# IntegratedSensor.net
KiCad netlist of a schematic drawn in EAGLE
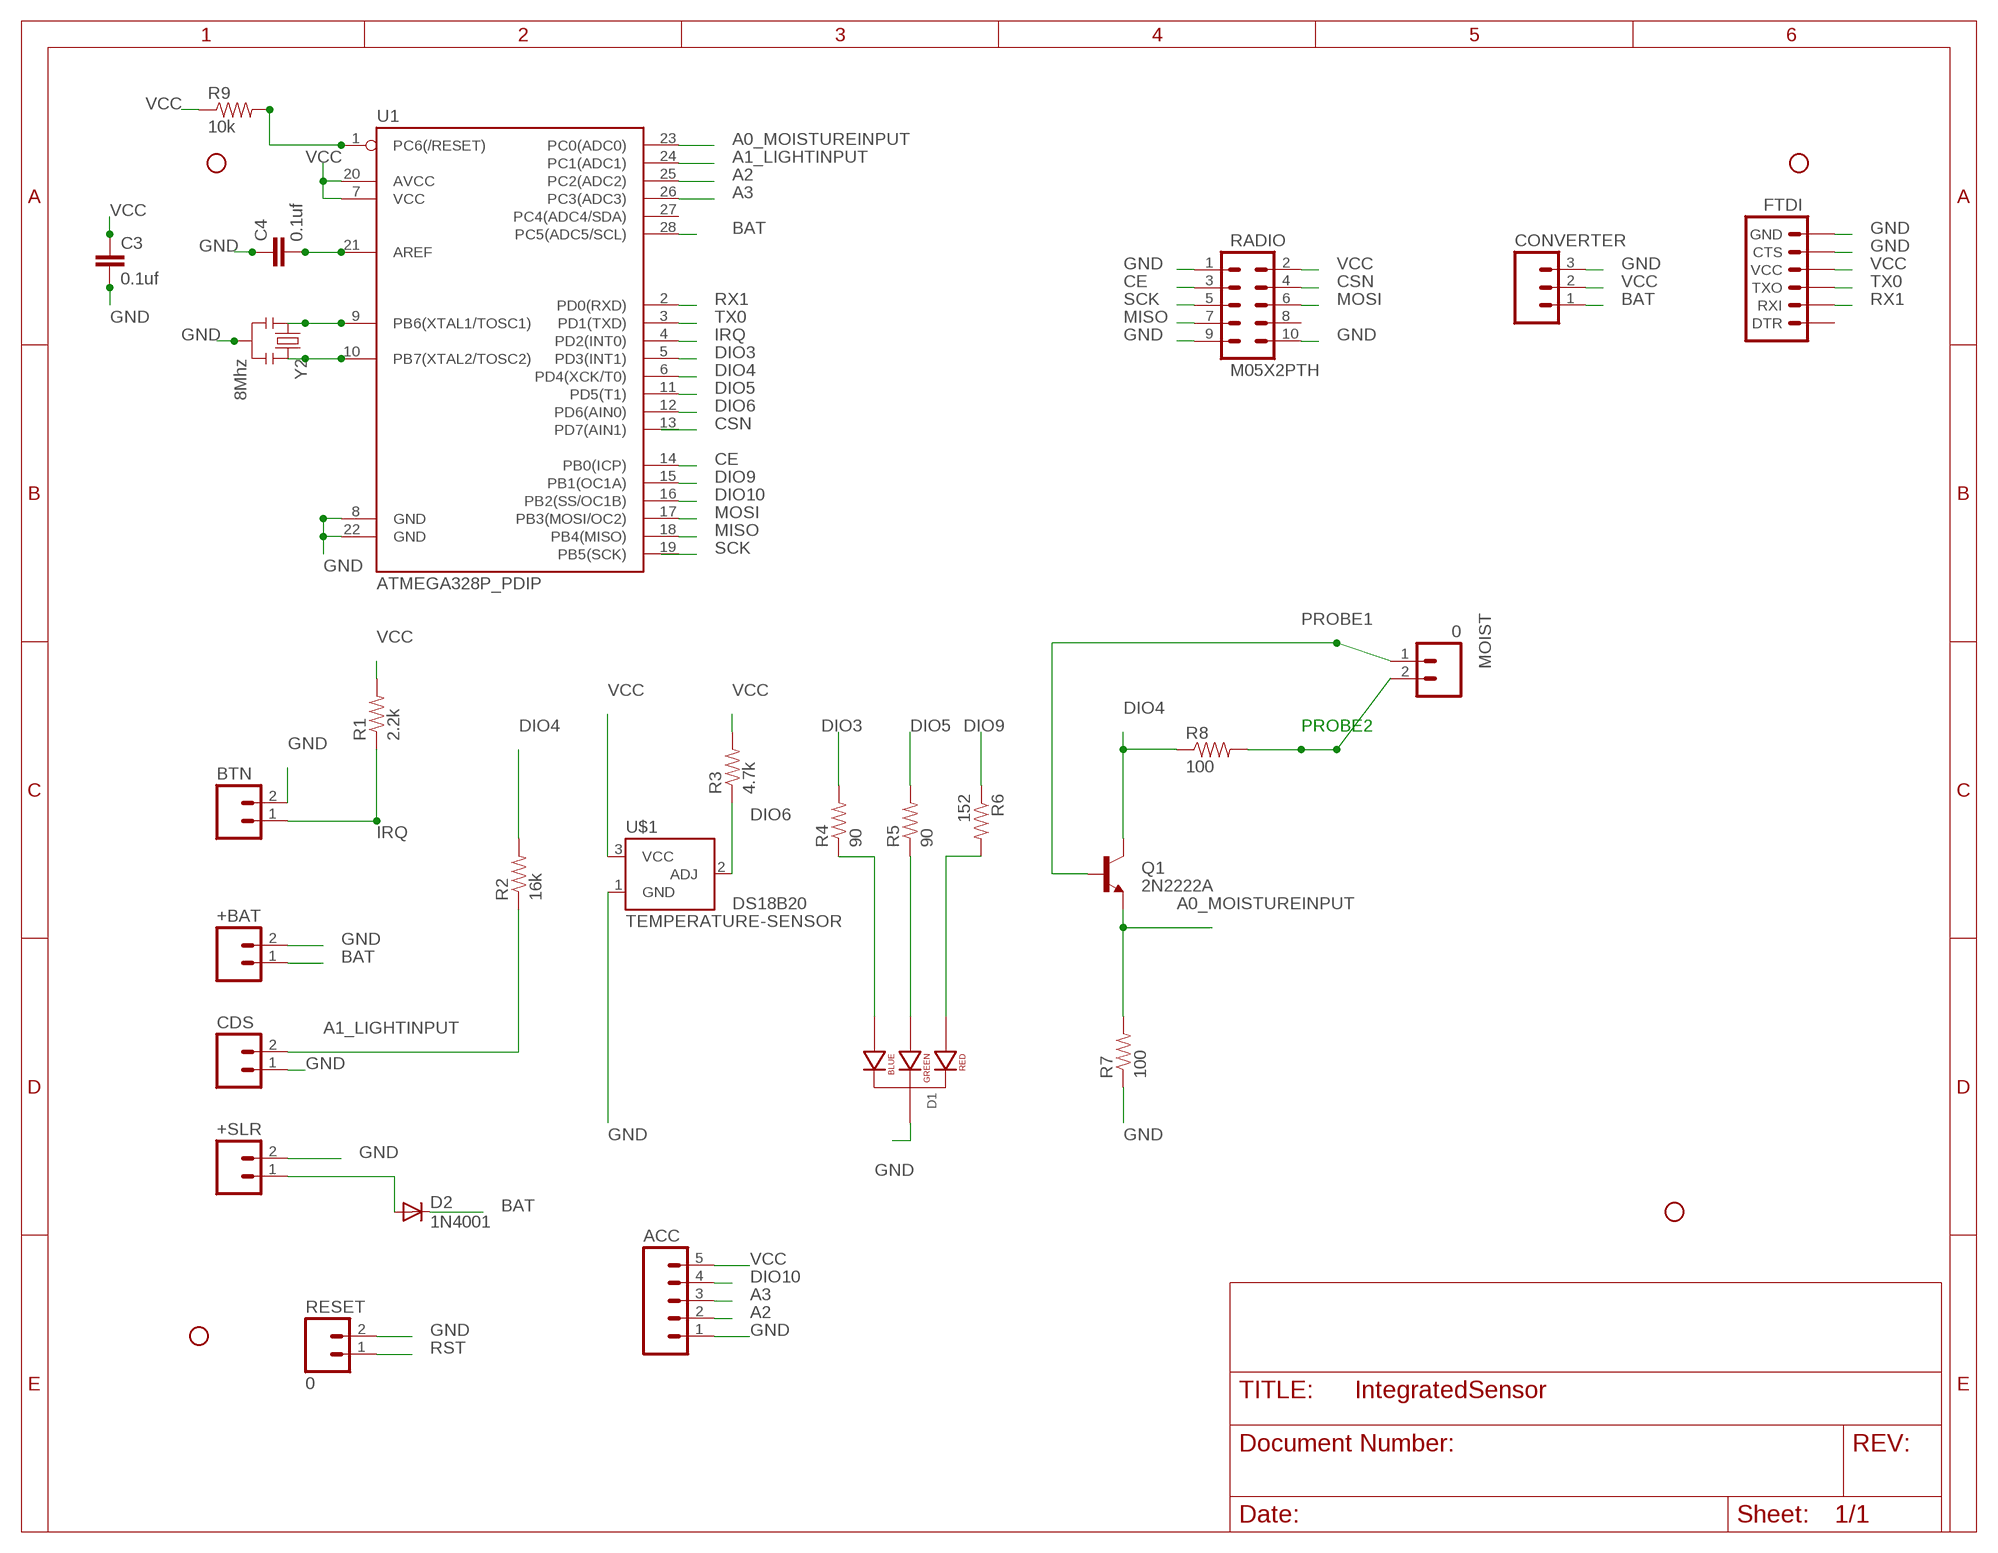
[diagram p0: schematic, sheet 1]

(export (version "E")
  (design (tool "Eeschema 10.0.6"))
  (components
    (comp (ref "+BAT")
      (value "M02PTH")
      (footprint "eagle-import:1X02")
      (libsource (lib "eagle-import") (part "M02PTH"))
    )
    (comp (ref "+SLR")
      (value "M02PTH")
      (footprint "eagle-import:1X02")
      (libsource (lib "eagle-import") (part "M02PTH"))
    )
    (comp (ref "ACC")
      (value "M05PTH")
      (footprint "eagle-import:1X05")
      (libsource (lib "eagle-import") (part "M05PTH"))
    )
    (comp (ref "BTN")
      (value "M02PTH")
      (footprint "eagle-import:1X02")
      (libsource (lib "eagle-import") (part "M02PTH"))
    )
    (comp (ref "C3")
      (value "0.1uf")
      (footprint "eagle-import:CAP-PTH-SMALL")
      (libsource (lib "eagle-import") (part "CAPPTH"))
    )
    (comp (ref "C4")
      (value "0.1uf")
      (footprint "eagle-import:CAP-PTH-SMALL")
      (libsource (lib "eagle-import") (part "CAPPTH"))
    )
    (comp (ref "CDS")
      (value "M02PTH")
      (footprint "eagle-import:1X02")
      (libsource (lib "eagle-import") (part "M02PTH"))
    )
    (comp (ref "CONVERTER")
      (value "M03PTH")
      (footprint "eagle-import:1X03")
      (libsource (lib "eagle-import") (part "M03PTH"))
    )
    (comp (ref "D1")
      (value "LED-RGB-CC-THRUCLEAR")
      (footprint "eagle-import:LED-RGB-THRU")
      (libsource (lib "eagle-import") (part "LED-RGB-CC-THRUCLEAR"))
    )
    (comp (ref "D2")
      (value "1N4001")
      (footprint "eagle-import:DIODE-1N4001")
      (libsource (lib "eagle-import") (part "DIODEPTH"))
    )
    (comp (ref "FTDI")
      (value "ARDUINO_SERIAL_PROGRAMPTH")
      (footprint "eagle-import:1X06")
      (libsource (lib "eagle-import") (part "ARDUINO_SERIAL_PROGRAMPTH"))
    )
    (comp (ref "MOIST")
      (value "0")
      (footprint "eagle-import:1X02")
      (libsource (lib "eagle-import") (part "M02PTH"))
    )
    (comp (ref "Q1")
      (value "2N2222A")
      (footprint "eagle-import:TO-92-AMMO")
      (libsource (lib "eagle-import") (part "TRANSISTOR_NPNTO-92-AMMO"))
    )
    (comp (ref "R1")
      (value "2.2k")
      (footprint "eagle-import:1_6W-RES")
      (libsource (lib "eagle-import") (part "RESISTORPTH-1/6W"))
    )
    (comp (ref "R2")
      (value "16k")
      (footprint "eagle-import:1_6W-RES")
      (libsource (lib "eagle-import") (part "RESISTORPTH-1/6W"))
    )
    (comp (ref "R3")
      (value "4.7k")
      (footprint "eagle-import:1_6W-RES")
      (libsource (lib "eagle-import") (part "RESISTORPTH-1/6W"))
    )
    (comp (ref "R4")
      (value "90")
      (footprint "eagle-import:1_6W-RES")
      (libsource (lib "eagle-import") (part "RESISTORPTH-1/6W"))
    )
    (comp (ref "R5")
      (value "90")
      (footprint "eagle-import:1_6W-RES")
      (libsource (lib "eagle-import") (part "RESISTORPTH-1/6W"))
    )
    (comp (ref "R6")
      (value "152")
      (footprint "eagle-import:1_6W-RES")
      (libsource (lib "eagle-import") (part "RESISTORPTH-1/6W"))
    )
    (comp (ref "R7")
      (value "100")
      (footprint "eagle-import:1_6W-RES")
      (libsource (lib "eagle-import") (part "RESISTORPTH-1/6W"))
    )
    (comp (ref "R8")
      (value "100")
      (footprint "eagle-import:1_6W-RES")
      (libsource (lib "eagle-import") (part "RESISTORPTH-1/6W"))
    )
    (comp (ref "R9")
      (value "10k")
      (footprint "eagle-import:1_6W-RES")
      (libsource (lib "eagle-import") (part "RESISTORPTH-1/6W"))
    )
    (comp (ref "RADIO")
      (value "M05X2PTH")
      (footprint "eagle-import:AVR_ICSP")
      (libsource (lib "eagle-import") (part "M05X2PTH"))
    )
    (comp (ref "RESET")
      (value "0")
      (footprint "eagle-import:1X02")
      (libsource (lib "eagle-import") (part "M02PTH"))
    )
    (comp (ref "STANDOFF1")
      (value "STAND-OFF")
      (footprint "eagle-import:STAND-OFF")
      (libsource (lib "eagle-import") (part "STAND-OFF"))
    )
    (comp (ref "STANDOFF2")
      (value "STAND-OFF")
      (footprint "eagle-import:STAND-OFF")
      (libsource (lib "eagle-import") (part "STAND-OFF"))
    )
    (comp (ref "STANDOFF3")
      (value "STAND-OFF")
      (footprint "eagle-import:STAND-OFF")
      (libsource (lib "eagle-import") (part "STAND-OFF"))
    )
    (comp (ref "STANDOFF4")
      (value "STAND-OFF")
      (footprint "eagle-import:STAND-OFF")
      (libsource (lib "eagle-import") (part "STAND-OFF"))
    )
    (comp (ref "U$1")
      (value "TEMPERATURE-SENSOR")
      (footprint "eagle-import:TO-92")
      (fields (field (name "PARTNAME") "DS18B20"))
      (libsource (lib "eagle-import") (part "TEMPERATURE-SENSOR"))
    )
    (comp (ref "U1")
      (value "ATMEGA328P_PDIP")
      (footprint "eagle-import:DIL28-3")
      (libsource (lib "eagle-import") (part "ATMEGA328P_PDIP"))
    )
    (comp (ref "Y2")
      (value "8Mhz")
      (footprint "eagle-import:RESONATOR-PTH")
      (libsource (lib "eagle-import") (part "RESONATORPTH"))
    )
  )
  (nets
    (net (code "1") (name "/A0_MOISTUREINPUT") (class "Default")
      (node (ref "Q1") (pin "1") (pinfunction "E_1") (pintype "passive"))
      (node (ref "R7") (pin "2") (pinfunction "2_2") (pintype "passive"))
      (node (ref "U1") (pin "23") (pinfunction "PC0(ADC0)_23") (pintype "bidirectional"))
    )
    (net (code "2") (name "/A1_LIGHTINPUT") (class "Default")
      (node (ref "CDS") (pin "2") (pinfunction "2_2") (pintype "passive"))
      (node (ref "R2") (pin "1") (pinfunction "1_1") (pintype "passive"))
      (node (ref "U1") (pin "24") (pinfunction "PC1(ADC1)_24") (pintype "bidirectional"))
    )
    (net (code "3") (name "/A2") (class "Default")
      (node (ref "ACC") (pin "2") (pinfunction "2_2") (pintype "passive"))
      (node (ref "U1") (pin "25") (pinfunction "PC2(ADC2)_25") (pintype "bidirectional"))
    )
    (net (code "4") (name "/A3") (class "Default")
      (node (ref "ACC") (pin "3") (pinfunction "3_3") (pintype "passive"))
      (node (ref "U1") (pin "26") (pinfunction "PC3(ADC3)_26") (pintype "bidirectional"))
    )
    (net (code "5") (name "/BAT") (class "Default")
      (node (ref "+BAT") (pin "1") (pinfunction "1_1") (pintype "passive"))
      (node (ref "CONVERTER") (pin "1") (pinfunction "1_1") (pintype "passive"))
      (node (ref "D2") (pin "C") (pinfunction "C_C") (pintype "passive"))
      (node (ref "U1") (pin "28") (pinfunction "PC5(ADC5/SCL)_28") (pintype "bidirectional"))
    )
    (net (code "6") (name "/CE") (class "Default")
      (node (ref "RADIO") (pin "3") (pinfunction "3_3") (pintype "passive"))
      (node (ref "U1") (pin "14") (pinfunction "PB0(ICP)_14") (pintype "bidirectional"))
    )
    (net (code "7") (name "/CSN") (class "Default")
      (node (ref "RADIO") (pin "4") (pinfunction "4_4") (pintype "passive"))
    )
    (net (code "8") (name "/DIO3") (class "Default")
      (node (ref "R4") (pin "2") (pinfunction "2_2") (pintype "passive"))
      (node (ref "U1") (pin "5") (pinfunction "PD3(INT1)_5") (pintype "bidirectional"))
    )
    (net (code "9") (name "/DIO4") (class "Default")
      (node (ref "Q1") (pin "3") (pinfunction "C_3") (pintype "passive"))
      (node (ref "R2") (pin "2") (pinfunction "2_2") (pintype "passive"))
      (node (ref "R8") (pin "1") (pinfunction "1_1") (pintype "passive"))
      (node (ref "U1") (pin "6") (pinfunction "PD4(XCK/T0)_6") (pintype "bidirectional"))
    )
    (net (code "10") (name "/DIO5") (class "Default")
      (node (ref "R5") (pin "2") (pinfunction "2_2") (pintype "passive"))
      (node (ref "U1") (pin "11") (pinfunction "PD5(T1)_11") (pintype "bidirectional"))
    )
    (net (code "11") (name "/DIO6") (class "Default")
      (node (ref "R3") (pin "1") (pinfunction "1_1") (pintype "passive"))
      (node (ref "U$1") (pin "2") (pinfunction "ADJ_2") (pintype "bidirectional"))
      (node (ref "U1") (pin "12") (pinfunction "PD6(AIN0)_12") (pintype "bidirectional"))
    )
    (net (code "12") (name "/DIO9") (class "Default")
      (node (ref "R6") (pin "1") (pinfunction "1_1") (pintype "passive"))
      (node (ref "U1") (pin "15") (pinfunction "PB1(OC1A)_15") (pintype "bidirectional"))
    )
    (net (code "13") (name "/DIO10") (class "Default")
      (node (ref "ACC") (pin "4") (pinfunction "4_4") (pintype "passive"))
      (node (ref "U1") (pin "16") (pinfunction "PB2(SS/OC1B)_16") (pintype "bidirectional"))
    )
    (net (code "14") (name "/GND") (class "Default")
      (node (ref "+BAT") (pin "2") (pinfunction "2_2") (pintype "passive"))
      (node (ref "+SLR") (pin "2") (pinfunction "2_2") (pintype "passive"))
      (node (ref "ACC") (pin "1") (pinfunction "1_1") (pintype "passive"))
      (node (ref "BTN") (pin "2") (pinfunction "2_2") (pintype "passive"))
      (node (ref "C3") (pin "2") (pinfunction "2_2") (pintype "passive"))
      (node (ref "C4") (pin "1") (pinfunction "1_1") (pintype "passive"))
      (node (ref "CDS") (pin "1") (pinfunction "1_1") (pintype "passive"))
      (node (ref "CONVERTER") (pin "3") (pinfunction "3_3") (pintype "passive"))
      (node (ref "D1") (pin "2") (pinfunction "CATHODE_2") (pintype "bidirectional"))
      (node (ref "FTDI") (pin "5") (pinfunction "CTS_5") (pintype "passive"))
      (node (ref "FTDI") (pin "6") (pinfunction "GND_6") (pintype "passive"))
      (node (ref "R7") (pin "1") (pinfunction "1_1") (pintype "passive"))
      (node (ref "RADIO") (pin "1") (pinfunction "1_1") (pintype "passive"))
      (node (ref "RADIO") (pin "10") (pinfunction "10_10") (pintype "passive"))
      (node (ref "RADIO") (pin "9") (pinfunction "9_9") (pintype "passive"))
      (node (ref "RESET") (pin "2") (pinfunction "2_2") (pintype "passive"))
      (node (ref "U$1") (pin "1") (pinfunction "GND_1") (pintype "bidirectional"))
      (node (ref "U1") (pin "22") (pinfunction "GND_22") (pintype "bidirectional"))
      (node (ref "U1") (pin "8") (pinfunction "GND_8") (pintype "bidirectional"))
      (node (ref "Y2") (pin "2") (pinfunction "2_2") (pintype "passive"))
    )
    (net (code "15") (name "/IRQ") (class "Default")
      (node (ref "BTN") (pin "1") (pinfunction "1_1") (pintype "passive"))
      (node (ref "R1") (pin "1") (pinfunction "1_1") (pintype "passive"))
      (node (ref "U1") (pin "4") (pinfunction "PD2(INT0)_4") (pintype "bidirectional"))
    )
    (net (code "16") (name "/MISO") (class "Default")
      (node (ref "RADIO") (pin "7") (pinfunction "7_7") (pintype "passive"))
      (node (ref "U1") (pin "18") (pinfunction "PB4(MISO)_18") (pintype "bidirectional"))
    )
    (net (code "17") (name "/MOSI") (class "Default")
      (node (ref "RADIO") (pin "6") (pinfunction "6_6") (pintype "passive"))
      (node (ref "U1") (pin "17") (pinfunction "PB3(MOSI/OC2)_17") (pintype "bidirectional"))
    )
    (net (code "18") (name "/PROBE1") (class "Default")
      (node (ref "MOIST") (pin "1") (pinfunction "1_1") (pintype "passive"))
      (node (ref "Q1") (pin "2") (pinfunction "B_2") (pintype "passive"))
    )
    (net (code "19") (name "/PROBE2") (class "Default")
      (node (ref "MOIST") (pin "2") (pinfunction "2_2") (pintype "passive"))
      (node (ref "R8") (pin "2") (pinfunction "2_2") (pintype "passive"))
    )
    (net (code "20") (name "/RST") (class "Default")
      (node (ref "RESET") (pin "1") (pinfunction "1_1") (pintype "passive"))
    )
    (net (code "21") (name "/RX1") (class "Default")
      (node (ref "FTDI") (pin "2") (pinfunction "RXI_2") (pintype "passive"))
      (node (ref "U1") (pin "2") (pinfunction "PD0(RXD)_2") (pintype "bidirectional"))
    )
    (net (code "22") (name "/SCK") (class "Default")
      (node (ref "RADIO") (pin "5") (pinfunction "5_5") (pintype "passive"))
    )
    (net (code "23") (name "/TX0") (class "Default")
      (node (ref "FTDI") (pin "3") (pinfunction "TXO_3") (pintype "passive"))
      (node (ref "U1") (pin "3") (pinfunction "PD1(TXD)_3") (pintype "bidirectional"))
    )
    (net (code "24") (name "/VCC") (class "Default")
      (node (ref "ACC") (pin "5") (pinfunction "5_5") (pintype "passive"))
      (node (ref "C3") (pin "1") (pinfunction "1_1") (pintype "passive"))
      (node (ref "CONVERTER") (pin "2") (pinfunction "2_2") (pintype "passive"))
      (node (ref "FTDI") (pin "4") (pinfunction "VCC_4") (pintype "passive"))
      (node (ref "R1") (pin "2") (pinfunction "2_2") (pintype "passive"))
      (node (ref "R3") (pin "2") (pinfunction "2_2") (pintype "passive"))
      (node (ref "R9") (pin "1") (pinfunction "1_1") (pintype "passive"))
      (node (ref "RADIO") (pin "2") (pinfunction "2_2") (pintype "passive"))
      (node (ref "U$1") (pin "3") (pinfunction "VCC_3") (pintype "bidirectional"))
      (node (ref "U1") (pin "20") (pinfunction "AVCC_20") (pintype "bidirectional"))
      (node (ref "U1") (pin "7") (pinfunction "VCC_7") (pintype "bidirectional"))
    )
    (net (code "25") (name "Net-(+SLR-Pad1)") (class "Default")
      (node (ref "+SLR") (pin "1") (pinfunction "1_1") (pintype "passive"))
      (node (ref "D2") (pin "A") (pinfunction "A_A") (pintype "passive"))
    )
    (net (code "26") (name "Net-(D1-BLUE_CATHODE)") (class "Default")
      (node (ref "D1") (pin "4") (pinfunction "BLUE_CATHODE_4") (pintype "bidirectional"))
      (node (ref "R4") (pin "1") (pinfunction "1_1") (pintype "passive"))
    )
    (net (code "27") (name "Net-(D1-GREEN_CATHODE)") (class "Default")
      (node (ref "D1") (pin "3") (pinfunction "GREEN_CATHODE_3") (pintype "bidirectional"))
      (node (ref "R5") (pin "1") (pinfunction "1_1") (pintype "passive"))
    )
    (net (code "28") (name "Net-(D1-RED_CATHODE)") (class "Default")
      (node (ref "D1") (pin "1") (pinfunction "RED_CATHODE_1") (pintype "bidirectional"))
      (node (ref "R6") (pin "2") (pinfunction "2_2") (pintype "passive"))
    )
    (net (code "29") (name "Net-(U1-AREF)") (class "Default")
      (node (ref "C4") (pin "2") (pinfunction "2_2") (pintype "passive"))
      (node (ref "U1") (pin "21") (pinfunction "AREF_21") (pintype "bidirectional"))
    )
    (net (code "30") (name "Net-(U1-PB6(XTAL1{slash}TOSC1))") (class "Default")
      (node (ref "U1") (pin "9") (pinfunction "PB6(XTAL1/TOSC1)_9") (pintype "bidirectional"))
      (node (ref "Y2") (pin "1") (pinfunction "1_1") (pintype "passive"))
    )
    (net (code "31") (name "Net-(U1-PB7(XTAL2{slash}TOSC2))") (class "Default")
      (node (ref "U1") (pin "10") (pinfunction "PB7(XTAL2/TOSC2)_10") (pintype "bidirectional"))
      (node (ref "Y2") (pin "3") (pinfunction "3_3") (pintype "passive"))
    )
    (net (code "32") (name "Net-(U1-PC6({slash}RESET))") (class "Default")
      (node (ref "R9") (pin "2") (pinfunction "2_2") (pintype "passive"))
      (node (ref "U1") (pin "1") (pinfunction "PC6(/RESET)_1") (pintype "bidirectional"))
    )
    (net (code "33") (name "unconnected-(FTDI-DTR-Pad1)") (class "Default")
      (node (ref "FTDI") (pin "1") (pinfunction "DTR_1") (pintype "passive"))
    )
    (net (code "34") (name "unconnected-(RADIO-Pad8)") (class "Default")
      (node (ref "RADIO") (pin "8") (pinfunction "8_8") (pintype "passive"))
    )
    (net (code "35") (name "unconnected-(U1-PB5(SCK)-Pad19)") (class "Default")
      (node (ref "U1") (pin "19") (pinfunction "PB5(SCK)_19") (pintype "bidirectional"))
    )
    (net (code "36") (name "unconnected-(U1-PC4(ADC4{slash}SDA)-Pad27)") (class "Default")
      (node (ref "U1") (pin "27") (pinfunction "PC4(ADC4/SDA)_27") (pintype "bidirectional"))
    )
    (net (code "37") (name "unconnected-(U1-PD7(AIN1)-Pad13)") (class "Default")
      (node (ref "U1") (pin "13") (pinfunction "PD7(AIN1)_13") (pintype "bidirectional"))
    )
  )
)
